# SpannungsverdopplerMit3LED_2.net
KiCad netlist of a schematic drawn in EAGLE
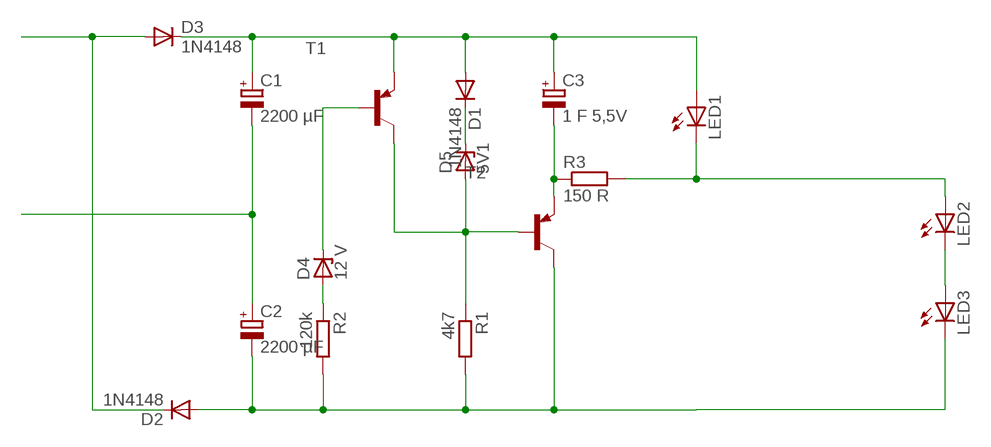
[diagram p0: schematic, sheet 1]

(export (version "E")
  (design (tool "Eeschema 10.0.6"))
  (components
    (comp (ref "C1")
      (value "2200 µF")
      (footprint "eagle-import:E5-10,5")
      (libsource (lib "eagle-import") (part "CPOL-EUE5-10.5"))
    )
    (comp (ref "C2")
      (value "2200 µF")
      (footprint "eagle-import:E5-10,5")
      (libsource (lib "eagle-import") (part "CPOL-EUE5-10.5"))
    )
    (comp (ref "C3")
      (value "1 F 5,5V")
      (footprint "eagle-import:E3,5-10")
      (libsource (lib "eagle-import") (part "CPOL-EUE3.5-10"))
    )
    (comp (ref "D1")
      (value "1N4148")
      (footprint "eagle-import:DO35-10")
      (libsource (lib "eagle-import") (part "1N4148DO35-10"))
    )
    (comp (ref "D2")
      (value "1N4148")
      (footprint "eagle-import:DO35-10")
      (libsource (lib "eagle-import") (part "1N4148DO35-10"))
    )
    (comp (ref "D3")
      (value "1N4148")
      (footprint "eagle-import:DO35-10")
      (libsource (lib "eagle-import") (part "1N4148DO35-10"))
    )
    (comp (ref "D4")
      (value "12 V")
      (footprint "eagle-import:SOD81")
      (libsource (lib "eagle-import") (part "BZD23"))
    )
    (comp (ref "D5")
      (value "5V1")
      (footprint "eagle-import:SOD81")
      (libsource (lib "eagle-import") (part "BZD23"))
    )
    (comp (ref "LED1")
      (value "LED10MM")
      (footprint "eagle-import:LED10MM")
      (libsource (lib "eagle-import") (part "LED10MM"))
    )
    (comp (ref "LED2")
      (value "LED10MM")
      (footprint "eagle-import:LED10MM")
      (libsource (lib "eagle-import") (part "LED10MM"))
    )
    (comp (ref "LED3")
      (value "LED10MM")
      (footprint "eagle-import:LED10MM")
      (libsource (lib "eagle-import") (part "LED10MM"))
    )
    (comp (ref "R1")
      (value "4k7")
      (footprint "eagle-import:0207_10")
      (libsource (lib "eagle-import") (part "R-EU_0207/10"))
    )
    (comp (ref "R2")
      (value "120k")
      (footprint "eagle-import:0207_10")
      (libsource (lib "eagle-import") (part "R-EU_0207/10"))
    )
    (comp (ref "R3")
      (value "150 R")
      (footprint "eagle-import:0207_10")
      (libsource (lib "eagle-import") (part "R-EU_0207/10"))
    )
    (comp (ref "T1")
      (value "2N2907-PNP-TO18-EBC")
      (footprint "eagle-import:TO18")
      (libsource (lib "eagle-import") (part "-PNP-TO18-EBC2N2907"))
    )
    (comp (ref "T2")
      (value "2N2907-PNP-TO18-EBC")
      (footprint "eagle-import:TO18")
      (libsource (lib "eagle-import") (part "-PNP-TO18-EBC2N2907"))
    )
  )
  (nets
    (net (code "1") (name "Net-(C1-Pad-)") (class "Default")
      (node (ref "C1") (pin "-") (pinfunction "-_-") (pintype "passive"))
      (node (ref "C2") (pin "+") (pinfunction "+_+") (pintype "passive"))
    )
    (net (code "2") (name "Net-(D1-PadC)") (class "Default")
      (node (ref "D1") (pin "C") (pinfunction "C_C") (pintype "passive"))
      (node (ref "D5") (pin "C") (pinfunction "C_C") (pintype "passive"))
    )
    (net (code "3") (name "Net-(D2-PadC)") (class "Default")
      (node (ref "D2") (pin "C") (pinfunction "C_C") (pintype "passive"))
      (node (ref "D3") (pin "A") (pinfunction "A_A") (pintype "passive"))
    )
    (net (code "4") (name "Net-(D4-PadA)") (class "Default")
      (node (ref "D4") (pin "A") (pinfunction "A_A") (pintype "passive"))
      (node (ref "R2") (pin "1") (pinfunction "1_1") (pintype "passive"))
    )
    (net (code "5") (name "Net-(LED1-C)") (class "Default")
      (node (ref "LED1") (pin "K") (pinfunction "C_K") (pintype "passive"))
      (node (ref "LED2") (pin "A") (pinfunction "A_A") (pintype "passive"))
      (node (ref "R3") (pin "2") (pinfunction "2_2") (pintype "passive"))
    )
    (net (code "6") (name "Net-(LED2-C)") (class "Default")
      (node (ref "LED2") (pin "K") (pinfunction "C_K") (pintype "passive"))
      (node (ref "LED3") (pin "A") (pinfunction "A_A") (pintype "passive"))
    )
    (net (code "7") (name "Net-(LED3-C)") (class "Default")
      (node (ref "C2") (pin "-") (pinfunction "-_-") (pintype "passive"))
      (node (ref "D2") (pin "A") (pinfunction "A_A") (pintype "passive"))
      (node (ref "LED3") (pin "K") (pinfunction "C_K") (pintype "passive"))
      (node (ref "R1") (pin "2") (pinfunction "2_2") (pintype "passive"))
      (node (ref "R2") (pin "2") (pinfunction "2_2") (pintype "passive"))
      (node (ref "T2") (pin "3") (pinfunction "C_3") (pintype "passive"))
    )
    (net (code "8") (name "Net-(T1-B)") (class "Default")
      (node (ref "D4") (pin "C") (pinfunction "C_C") (pintype "passive"))
      (node (ref "T1") (pin "2") (pinfunction "B_2") (pintype "passive"))
    )
    (net (code "9") (name "Net-(T1-C)") (class "Default")
      (node (ref "D5") (pin "A") (pinfunction "A_A") (pintype "passive"))
      (node (ref "R1") (pin "1") (pinfunction "1_1") (pintype "passive"))
      (node (ref "T1") (pin "3") (pinfunction "C_3") (pintype "passive"))
      (node (ref "T2") (pin "2") (pinfunction "B_2") (pintype "passive"))
    )
    (net (code "10") (name "Net-(T1-E)") (class "Default")
      (node (ref "C1") (pin "+") (pinfunction "+_+") (pintype "passive"))
      (node (ref "C3") (pin "+") (pinfunction "+_+") (pintype "passive"))
      (node (ref "D1") (pin "A") (pinfunction "A_A") (pintype "passive"))
      (node (ref "D3") (pin "C") (pinfunction "C_C") (pintype "passive"))
      (node (ref "LED1") (pin "A") (pinfunction "A_A") (pintype "passive"))
      (node (ref "T1") (pin "1") (pinfunction "E_1") (pintype "passive"))
    )
    (net (code "11") (name "Net-(T2-E)") (class "Default")
      (node (ref "C3") (pin "-") (pinfunction "-_-") (pintype "passive"))
      (node (ref "R3") (pin "1") (pinfunction "1_1") (pintype "passive"))
      (node (ref "T2") (pin "1") (pinfunction "E_1") (pintype "passive"))
    )
  )
)
